# UART_to_USB-OTG_USB.net
KiCad netlist of a schematic drawn in Altium Designer
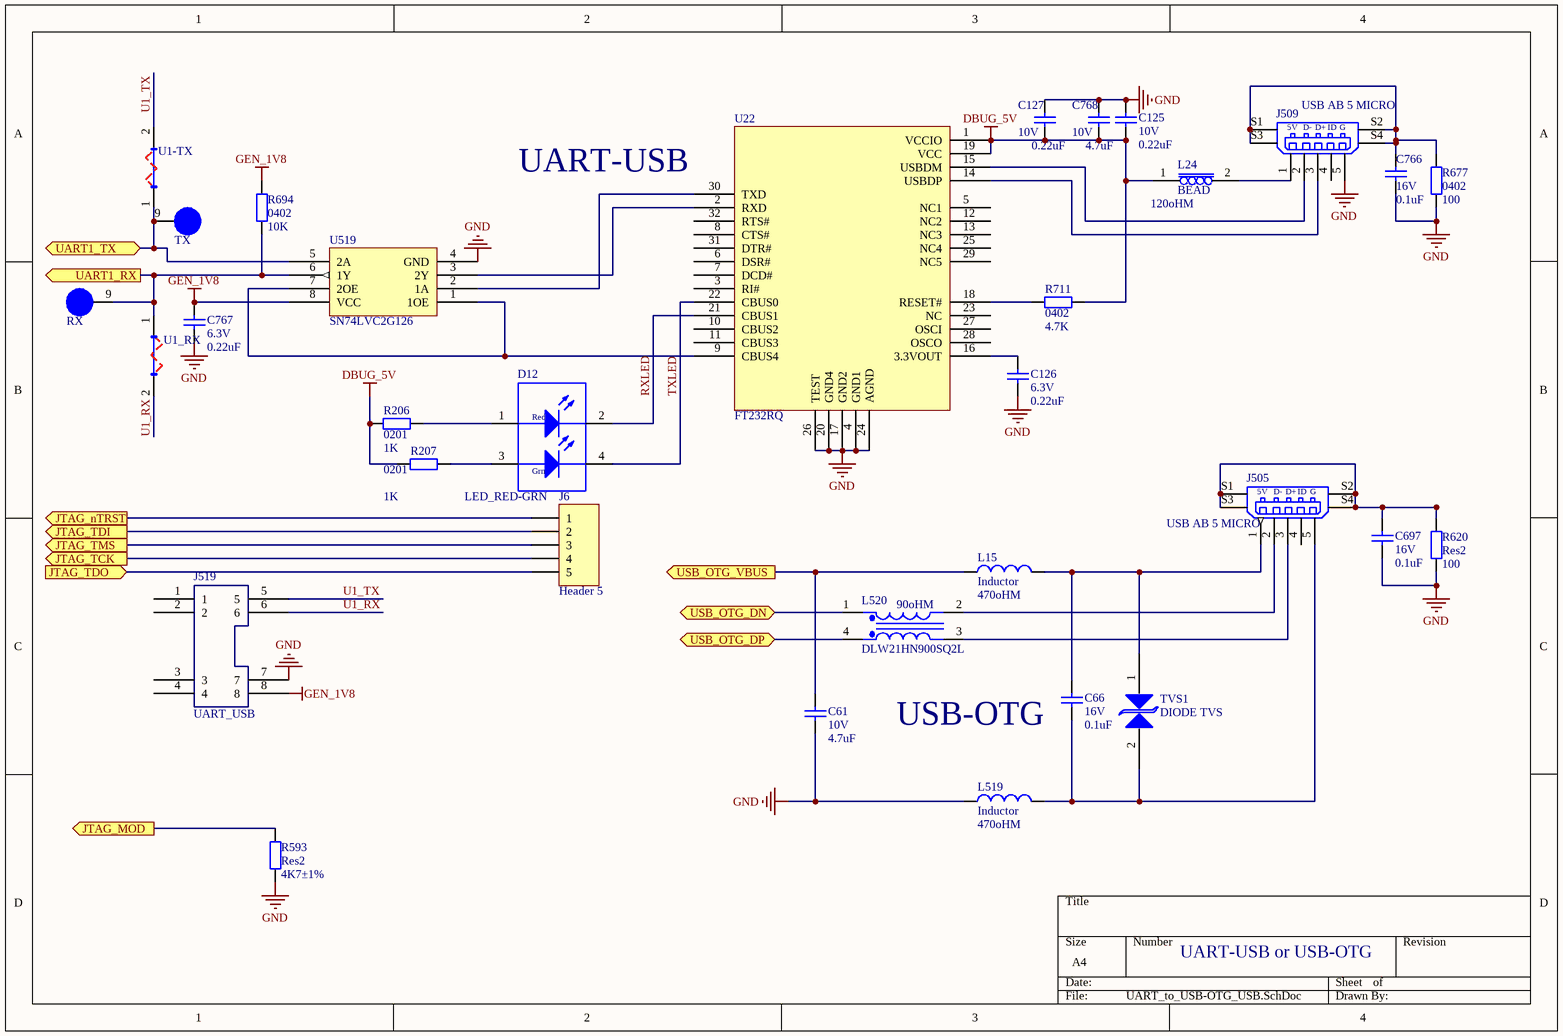
[diagram p0: UART_to_USB-OTG_USB.SchDoc]

(export (version "E")
  (design (tool "Eeschema 10.0.6"))
  (components
    (comp (ref "C61")
      (value "10V")
      (footprint "0603")
      (description "Capacitor")
      (fields (field (name "ALTIUM_VALUE") "4.7uF") (field (name "PUBLISHER") "Altium Limited"))
      (libsource (lib "Miscellaneous Devices") (part "Cap"))
    )
    (comp (ref "C66")
      (value "16V")
      (footprint "0402")
      (description "Capacitor")
      (fields (field (name "ALTIUM_VALUE") "0.1uF") (field (name "PUBLISHER") "Altium Limited"))
      (libsource (lib "Miscellaneous Devices") (part "Cap"))
    )
    (comp (ref "C125")
      (value "10V")
      (footprint "0201")
      (description "Capacitor")
      (fields (field (name "ALTIUM_VALUE") "0.22uF") (field (name "PUBLISHER") "Altium Limited"))
      (libsource (lib "Miscellaneous Devices") (part "Cap"))
    )
    (comp (ref "C126")
      (value "6.3V")
      (footprint "0201")
      (description "Capacitor")
      (fields (field (name "ALTIUM_VALUE") "0.22uF") (field (name "PUBLISHER") "Altium Limited"))
      (libsource (lib "Miscellaneous Devices") (part "Cap"))
    )
    (comp (ref "C127")
      (value "10V")
      (footprint "0201")
      (description "Capacitor")
      (fields (field (name "ALTIUM_VALUE") "0.22uF") (field (name "PUBLISHER") "Altium Limited"))
      (libsource (lib "Miscellaneous Devices") (part "Cap"))
    )
    (comp (ref "C697")
      (value "16V")
      (footprint "0402")
      (description "Capacitor")
      (fields (field (name "ALTIUM_VALUE") "0.1uF") (field (name "PUBLISHER") "Altium Limited"))
      (libsource (lib "Miscellaneous Devices") (part "Cap"))
    )
    (comp (ref "C766")
      (value "16V")
      (footprint "0402")
      (description "Capacitor")
      (fields (field (name "ALTIUM_VALUE") "0.1uF") (field (name "PUBLISHER") "Altium Limited"))
      (libsource (lib "Miscellaneous Devices") (part "Cap"))
    )
    (comp (ref "C767")
      (value "6.3V")
      (footprint "0201")
      (description "Capacitor")
      (fields (field (name "ALTIUM_VALUE") "0.22uF") (field (name "PUBLISHER") "Altium Limited"))
      (libsource (lib "Miscellaneous Devices") (part "Cap"))
    )
    (comp (ref "C768")
      (value "10V")
      (footprint "0603")
      (description "Capacitor")
      (fields (field (name "ALTIUM_VALUE") "4.7uF") (field (name "PUBLISHER") "Altium Limited"))
      (libsource (lib "Miscellaneous Devices") (part "Cap"))
    )
    (comp (ref "D12")
      (value "LED_RED-GRN")
      (footprint "APB3025ESGC-F01-SMT")
      (libsource (lib "IMX6DL") (part "APB3025ESGC-F01"))
    )
    (comp (ref "J6")
      (value "Header 5")
      (footprint "HDR1X5")
      (description "Header, 5-Pin")
      (fields (field (name "PUBLISHER") "Altium Limited"))
      (libsource (lib "Miscellaneous Connectors") (part "Header 5"))
    )
    (comp (ref "J505")
      (value "USB AB 5 MICRO")
      (footprint "micro-USB-port")
      (libsource (lib "IMX6DL") (part "USB AB 5 MICRO"))
    )
    (comp (ref "J509")
      (value "USB AB 5 MICRO")
      (footprint "micro-USB-port")
      (libsource (lib "IMX6DL") (part "USB AB 5 MICRO"))
    )
    (comp (ref "J519")
      (value "UART_USB")
      (footprint "DC3-8")
      (libsource (lib "IMX6DL") (part "JTAG_hornsocket8P"))
    )
    (comp (ref "L15")
      (value "Inductor")
      (footprint "0603")
      (fields (field (name "ALTIUM_VALUE") "470oHM") (field (name "PUBLISHER") "Altium Limited"))
      (libsource (lib "Miscellaneous Devices") (part "Inductor"))
    )
    (comp (ref "L24")
      (value "BEAD")
      (footprint "0603")
      (fields (field (name "ALTIUM_UNNAMED_1") "120oHM"))
      (libsource (lib "IMX6DL") (part "magnetic BEAD"))
    )
    (comp (ref "L519")
      (value "Inductor")
      (footprint "0603")
      (fields (field (name "ALTIUM_VALUE") "470oHM") (field (name "PUBLISHER") "Altium Limited"))
      (libsource (lib "Miscellaneous Devices") (part "Inductor"))
    )
    (comp (ref "L520")
      (value "DLW21HN900SQ2L")
      (footprint "DLW21HN900SQ2L-0805")
      (fields (field (name "ALTIUM_UNNAMED_1") "90oHM"))
      (libsource (lib "IMX6DL") (part "DLW21HN900SQ2L"))
    )
    (comp (ref "R206")
      (value "0201")
      (footprint "0201")
      (description "Resistor")
      (fields (field (name "ALTIUM_VALUE") "1K") (field (name "PUBLISHER") "Altium Limited"))
      (libsource (lib "Miscellaneous Devices") (part "Res2"))
    )
    (comp (ref "R207")
      (value "0201")
      (footprint "0201")
      (description "Resistor")
      (fields (field (name "ALTIUM_VALUE") "1K") (field (name "PUBLISHER") "Altium Limited"))
      (libsource (lib "Miscellaneous Devices") (part "Res2"))
    )
    (comp (ref "R593")
      (value "Res2")
      (footprint "0402")
      (description "Resistor")
      (fields (field (name "ALTIUM_VALUE") "4K7±1%") (field (name "PUBLISHER") "Altium Limited"))
      (libsource (lib "") (part "Res2_1"))
    )
    (comp (ref "R620")
      (value "Res2")
      (footprint "0402")
      (description "Resistor")
      (fields (field (name "ALTIUM_VALUE") "100") (field (name "PUBLISHER") "Altium Limited"))
      (libsource (lib "") (part "Res2_1"))
    )
    (comp (ref "R677")
      (value "0402")
      (footprint "0402")
      (description "Resistor")
      (fields (field (name "ALTIUM_VALUE") "100") (field (name "PUBLISHER") "Altium Limited"))
      (libsource (lib "") (part "Res2_1"))
    )
    (comp (ref "R694")
      (value "0402")
      (footprint "0402")
      (description "Resistor")
      (fields (field (name "ALTIUM_VALUE") "10K") (field (name "PUBLISHER") "Altium Limited"))
      (libsource (lib "") (part "Res2_1"))
    )
    (comp (ref "R711")
      (value "0402")
      (footprint "0402")
      (description "Resistor")
      (fields (field (name "ALTIUM_VALUE") "4.7K") (field (name "PUBLISHER") "Altium Limited"))
      (libsource (lib "Miscellaneous Devices") (part "Res2"))
    )
    (comp (ref "RX") (value "TP test") (footprint "TP") (libsource (lib "IMX6DL") (part "TP test")))
    (comp (ref "TVS1")
      (value "DIODE TVS")
      (footprint "ESD9B3.3ST5G-SOD923")
      (libsource (lib "IMX6DL") (part "DIODE TVS"))
    )
    (comp (ref "TX") (value "TP test") (footprint "TP") (libsource (lib "IMX6DL") (part "TP test")))
    (comp (ref "U1-TX")
      (value "SHORT")
      (footprint "SHORT_SH")
      (libsource (lib "IMX6DL") (part "SOLDER SHORT"))
    )
    (comp (ref "U1_RX")
      (value "SHORT")
      (footprint "SHORT_SH")
      (libsource (lib "IMX6DL") (part "SOLDER SHORT"))
    )
    (comp (ref "U22")
      (value "FT232RQ")
      (footprint "FT232RQ-QFN32")
      (libsource (lib "IMX6DL") (part "FT232RQ"))
    )
    (comp (ref "U519")
      (value "SN74LVC2G126")
      (footprint "SN74LVC2G126-SSOP8")
      (libsource (lib "IMX6DL") (part "SN74LVC2G126"))
    )
  )
  (nets
    (net (code "1") (name "/JTAG_MOD") (class "Default")
      (node (ref "R593") (pin "2") (pinfunction "2_2") (pintype "passive"))
    )
    (net (code "2") (name "/JTAG_TCK") (class "Default")
      (node (ref "J6") (pin "4") (pinfunction "4_4") (pintype "passive"))
    )
    (net (code "3") (name "/JTAG_TDI") (class "Default")
      (node (ref "J6") (pin "2") (pinfunction "2_2") (pintype "passive"))
    )
    (net (code "4") (name "/JTAG_TDO") (class "Default")
      (node (ref "J6") (pin "5") (pinfunction "5_5") (pintype "passive"))
    )
    (net (code "5") (name "/JTAG_TMS") (class "Default")
      (node (ref "J6") (pin "3") (pinfunction "3_3") (pintype "passive"))
    )
    (net (code "6") (name "/JTAG_nTRST") (class "Default")
      (node (ref "J6") (pin "1") (pinfunction "1_1") (pintype "passive"))
    )
    (net (code "7") (name "/RXLED") (class "Default")
      (node (ref "D12") (pin "2") (pinfunction "GND_2") (pintype "passive"))
      (node (ref "U22") (pin "21") (pinfunction "CBUS1_21") (pintype "passive"))
    )
    (net (code "8") (name "/TXLED") (class "Default")
      (node (ref "D12") (pin "4") (pinfunction "GND_4") (pintype "passive"))
      (node (ref "U22") (pin "22") (pinfunction "CBUS0_22") (pintype "passive"))
    )
    (net (code "9") (name "/U1_RX") (class "Default")
      (node (ref "J519") (pin "6") (pinfunction "6_6") (pintype "passive"))
      (node (ref "U1_RX") (pin "2") (pinfunction "VCCIO_2") (pintype "passive"))
    )
    (net (code "10") (name "/U1_TX") (class "Default")
      (node (ref "J519") (pin "5") (pinfunction "5_5") (pintype "passive"))
      (node (ref "U1-TX") (pin "2") (pinfunction "VCCIO_2") (pintype "passive"))
    )
    (net (code "11") (name "/UART1_RX") (class "Default")
      (node (ref "R694") (pin "1") (pinfunction "1_1") (pintype "passive"))
      (node (ref "RX") (pin "9") (pinfunction "S_9") (pintype "passive"))
      (node (ref "U1_RX") (pin "1") (pinfunction "VCCIO_1") (pintype "passive"))
      (node (ref "U519") (pin "6") (pinfunction "1Y_6") (pintype "output"))
    )
    (net (code "12") (name "/UART1_TX") (class "Default")
      (node (ref "TX") (pin "9") (pinfunction "S_9") (pintype "passive"))
      (node (ref "U1-TX") (pin "1") (pinfunction "VCCIO_1") (pintype "passive"))
      (node (ref "U519") (pin "5") (pinfunction "2A_5") (pintype "passive"))
    )
    (net (code "13") (name "/USB_OTG_DN") (class "Default")
      (node (ref "L520") (pin "1") (pinfunction "VSS11_1") (pintype "passive"))
    )
    (net (code "14") (name "/USB_OTG_DP") (class "Default")
      (node (ref "L520") (pin "4") (pinfunction "VSS14_4") (pintype "passive"))
    )
    (net (code "15") (name "/USB_OTG_VBUS") (class "Default")
      (node (ref "C61") (pin "2") (pinfunction "2_2") (pintype "passive"))
      (node (ref "L15") (pin "1") (pinfunction "1_1") (pintype "passive"))
    )
    (net (code "16") (name "DBUG_5V") (class "Default")
      (node (ref "C125") (pin "2") (pinfunction "2_2") (pintype "passive"))
      (node (ref "C127") (pin "2") (pinfunction "2_2") (pintype "passive"))
      (node (ref "C768") (pin "1") (pinfunction "1_1") (pintype "passive"))
      (node (ref "L24") (pin "1") (pinfunction "VSS3_1") (pintype "passive"))
      (node (ref "R206") (pin "1") (pinfunction "1_1") (pintype "passive"))
      (node (ref "R207") (pin "1") (pinfunction "1_1") (pintype "passive"))
      (node (ref "R711") (pin "2") (pinfunction "2_2") (pintype "passive"))
      (node (ref "U22") (pin "1") (pinfunction "VCCIO_1") (pintype "passive"))
      (node (ref "U22") (pin "19") (pinfunction "VCC_19") (pintype "passive"))
    )
    (net (code "17") (name "GEN_1V8") (class "Default")
      (node (ref "C767") (pin "1") (pinfunction "1_1") (pintype "passive"))
      (node (ref "J519") (pin "8") (pinfunction "8_8") (pintype "passive"))
      (node (ref "R694") (pin "2") (pinfunction "2_2") (pintype "passive"))
      (node (ref "U519") (pin "8") (pinfunction "VCC_8") (pintype "passive"))
    )
    (net (code "18") (name "GND") (class "Default")
      (node (ref "C125") (pin "1") (pinfunction "1_1") (pintype "passive"))
      (node (ref "C126") (pin "2") (pinfunction "2_2") (pintype "passive"))
      (node (ref "C127") (pin "1") (pinfunction "1_1") (pintype "passive"))
      (node (ref "C61") (pin "1") (pinfunction "1_1") (pintype "passive"))
      (node (ref "C697") (pin "1") (pinfunction "1_1") (pintype "passive"))
      (node (ref "C766") (pin "1") (pinfunction "1_1") (pintype "passive"))
      (node (ref "C767") (pin "2") (pinfunction "2_2") (pintype "passive"))
      (node (ref "C768") (pin "2") (pinfunction "2_2") (pintype "passive"))
      (node (ref "J509") (pin "5") (pinfunction "GND_5") (pintype "passive"))
      (node (ref "J519") (pin "7") (pinfunction "7_7") (pintype "passive"))
      (node (ref "L519") (pin "1") (pinfunction "1_1") (pintype "passive"))
      (node (ref "R593") (pin "1") (pinfunction "1_1") (pintype "passive"))
      (node (ref "R620") (pin "1") (pinfunction "1_1") (pintype "passive"))
      (node (ref "R677") (pin "1") (pinfunction "1_1") (pintype "passive"))
      (node (ref "U22") (pin "17") (pinfunction "GND2_17") (pintype "passive"))
      (node (ref "U22") (pin "20") (pinfunction "GND4_20") (pintype "passive"))
      (node (ref "U22") (pin "24") (pinfunction "AGND_24") (pintype "passive"))
      (node (ref "U22") (pin "26") (pinfunction "TEST_26") (pintype "passive"))
      (node (ref "U22") (pin "4") (pinfunction "GND1_4") (pintype "passive"))
      (node (ref "U519") (pin "4") (pinfunction "GND_4") (pintype "passive"))
    )
    (net (code "19") (name "Net-(D12-GND-Pad1)") (class "Default")
      (node (ref "D12") (pin "1") (pinfunction "GND_1") (pintype "passive"))
      (node (ref "R206") (pin "2") (pinfunction "2_2") (pintype "passive"))
    )
    (net (code "20") (name "Net-(D12-GND-Pad3)") (class "Default")
      (node (ref "D12") (pin "3") (pinfunction "GND_3") (pintype "passive"))
      (node (ref "R207") (pin "2") (pinfunction "2_2") (pintype "passive"))
    )
    (net (code "21") (name "Net-(J505-6)") (class "Default")
      (node (ref "C697") (pin "2") (pinfunction "2_2") (pintype "passive"))
      (node (ref "J505") (pin "S1") (pinfunction "6_S1") (pintype "passive"))
      (node (ref "J505") (pin "S2") (pinfunction "7_S2") (pintype "passive"))
      (node (ref "J505") (pin "S3") (pinfunction "8_S3") (pintype "passive"))
      (node (ref "J505") (pin "S4") (pinfunction "9_S4") (pintype "passive"))
      (node (ref "R620") (pin "2") (pinfunction "2_2") (pintype "passive"))
    )
    (net (code "22") (name "Net-(J509-6)") (class "Default")
      (node (ref "C766") (pin "2") (pinfunction "2_2") (pintype "passive"))
      (node (ref "J509") (pin "S1") (pinfunction "6_S1") (pintype "passive"))
      (node (ref "J509") (pin "S2") (pinfunction "7_S2") (pintype "passive"))
      (node (ref "J509") (pin "S3") (pinfunction "8_S3") (pintype "passive"))
      (node (ref "J509") (pin "S4") (pinfunction "9_S4") (pintype "passive"))
      (node (ref "R677") (pin "2") (pinfunction "2_2") (pintype "passive"))
    )
    (net (code "23") (name "Net-(L24-VSS4)") (class "Default")
      (node (ref "J509") (pin "1") (pinfunction "GND_1") (pintype "passive"))
      (node (ref "L24") (pin "2") (pinfunction "VSS4_2") (pintype "passive"))
    )
    (net (code "24") (name "Net-(L520-VSS12)") (class "Default")
      (node (ref "J505") (pin "2") (pinfunction "GND_2") (pintype "passive"))
      (node (ref "L520") (pin "2") (pinfunction "VSS12_2") (pintype "passive"))
    )
    (net (code "25") (name "Net-(L520-VSS13)") (class "Default")
      (node (ref "J505") (pin "3") (pinfunction "GND_3") (pintype "passive"))
      (node (ref "L520") (pin "3") (pinfunction "VSS13_3") (pintype "passive"))
    )
    (net (code "26") (name "Net-(TVS1-VSS5)") (class "Default")
      (node (ref "C66") (pin "1") (pinfunction "1_1") (pintype "passive"))
      (node (ref "J505") (pin "5") (pinfunction "GND_5") (pintype "passive"))
      (node (ref "L519") (pin "2") (pinfunction "2_2") (pintype "passive"))
      (node (ref "TVS1") (pin "2") (pinfunction "VSS5_2") (pintype "passive"))
    )
    (net (code "27") (name "Net-(TVS1-VSS6)") (class "Default")
      (node (ref "C66") (pin "2") (pinfunction "2_2") (pintype "passive"))
      (node (ref "J505") (pin "1") (pinfunction "GND_1") (pintype "passive"))
      (node (ref "L15") (pin "2") (pinfunction "2_2") (pintype "passive"))
      (node (ref "TVS1") (pin "1") (pinfunction "VSS6_1") (pintype "passive"))
    )
    (net (code "28") (name "Net-(U22-3.3VOUT)") (class "Default")
      (node (ref "C126") (pin "1") (pinfunction "1_1") (pintype "passive"))
      (node (ref "U22") (pin "16") (pinfunction "3.3VOUT_16") (pintype "passive"))
    )
    (net (code "29") (name "Net-(U22-CBUS4)") (class "Default")
      (node (ref "U22") (pin "9") (pinfunction "CBUS4_9") (pintype "passive"))
      (node (ref "U519") (pin "1") (pinfunction "1OE_1") (pintype "passive"))
      (node (ref "U519") (pin "7") (pinfunction "2OE_7") (pintype "passive"))
    )
    (net (code "30") (name "Net-(U22-RESET#)") (class "Default")
      (node (ref "R711") (pin "1") (pinfunction "1_1") (pintype "passive"))
      (node (ref "U22") (pin "18") (pinfunction "RESET#_18") (pintype "passive"))
    )
    (net (code "31") (name "Net-(U22-RXD)") (class "Default")
      (node (ref "U22") (pin "2") (pinfunction "RXD_2") (pintype "passive"))
      (node (ref "U519") (pin "3") (pinfunction "2Y_3") (pintype "passive"))
    )
    (net (code "32") (name "Net-(U22-TXD)") (class "Default")
      (node (ref "U22") (pin "30") (pinfunction "TXD_30") (pintype "passive"))
      (node (ref "U519") (pin "2") (pinfunction "1A_2") (pintype "passive"))
    )
    (net (code "33") (name "Net-(U22-USBDM)") (class "Default")
      (node (ref "J509") (pin "2") (pinfunction "GND_2") (pintype "passive"))
      (node (ref "U22") (pin "15") (pinfunction "USBDM_15") (pintype "passive"))
    )
    (net (code "34") (name "Net-(U22-USBDP)") (class "Default")
      (node (ref "J509") (pin "3") (pinfunction "GND_3") (pintype "passive"))
      (node (ref "U22") (pin "14") (pinfunction "USBDP_14") (pintype "passive"))
    )
    (net (code "35") (name "unconnected-(J505-GND-Pad4)") (class "Default")
      (node (ref "J505") (pin "4") (pinfunction "GND_4") (pintype "passive"))
    )
    (net (code "36") (name "unconnected-(J509-GND-Pad4)") (class "Default")
      (node (ref "J509") (pin "4") (pinfunction "GND_4") (pintype "passive"))
    )
    (net (code "37") (name "unconnected-(J519-Pad1)") (class "Default")
      (node (ref "J519") (pin "1") (pinfunction "1_1") (pintype "passive"))
    )
    (net (code "38") (name "unconnected-(J519-Pad2)") (class "Default")
      (node (ref "J519") (pin "2") (pinfunction "2_2") (pintype "passive"))
    )
    (net (code "39") (name "unconnected-(J519-Pad3)") (class "Default")
      (node (ref "J519") (pin "3") (pinfunction "3_3") (pintype "passive"))
    )
    (net (code "40") (name "unconnected-(J519-Pad4)") (class "Default")
      (node (ref "J519") (pin "4") (pinfunction "4_4") (pintype "passive"))
    )
    (net (code "41") (name "unconnected-(U22-CBUS2-Pad10)") (class "Default")
      (node (ref "U22") (pin "10") (pinfunction "CBUS2_10") (pintype "passive"))
    )
    (net (code "42") (name "unconnected-(U22-CBUS3-Pad11)") (class "Default")
      (node (ref "U22") (pin "11") (pinfunction "CBUS3_11") (pintype "passive"))
    )
    (net (code "43") (name "unconnected-(U22-CTS#-Pad8)") (class "Default")
      (node (ref "U22") (pin "8") (pinfunction "CTS#_8") (pintype "passive"))
    )
    (net (code "44") (name "unconnected-(U22-DCD#-Pad7)") (class "Default")
      (node (ref "U22") (pin "7") (pinfunction "DCD#_7") (pintype "passive"))
    )
    (net (code "45") (name "unconnected-(U22-DSR#-Pad6)") (class "Default")
      (node (ref "U22") (pin "6") (pinfunction "DSR#_6") (pintype "passive"))
    )
    (net (code "46") (name "unconnected-(U22-DTR#-Pad31)") (class "Default")
      (node (ref "U22") (pin "31") (pinfunction "DTR#_31") (pintype "passive"))
    )
    (net (code "47") (name "unconnected-(U22-NC-Pad23)") (class "Default")
      (node (ref "U22") (pin "23") (pinfunction "NC_23") (pintype "passive"))
    )
    (net (code "48") (name "unconnected-(U22-NC1-Pad5)") (class "Default")
      (node (ref "U22") (pin "5") (pinfunction "NC1_5") (pintype "passive"))
    )
    (net (code "49") (name "unconnected-(U22-NC2-Pad12)") (class "Default")
      (node (ref "U22") (pin "12") (pinfunction "NC2_12") (pintype "passive"))
    )
    (net (code "50") (name "unconnected-(U22-NC3-Pad13)") (class "Default")
      (node (ref "U22") (pin "13") (pinfunction "NC3_13") (pintype "passive"))
    )
    (net (code "51") (name "unconnected-(U22-NC4-Pad25)") (class "Default")
      (node (ref "U22") (pin "25") (pinfunction "NC4_25") (pintype "passive"))
    )
    (net (code "52") (name "unconnected-(U22-NC5-Pad29)") (class "Default")
      (node (ref "U22") (pin "29") (pinfunction "NC5_29") (pintype "passive"))
    )
    (net (code "53") (name "unconnected-(U22-OSCI-Pad27)") (class "Default")
      (node (ref "U22") (pin "27") (pinfunction "OSCI_27") (pintype "passive"))
    )
    (net (code "54") (name "unconnected-(U22-OSCO-Pad28)") (class "Default")
      (node (ref "U22") (pin "28") (pinfunction "OSCO_28") (pintype "passive"))
    )
    (net (code "55") (name "unconnected-(U22-RI#-Pad3)") (class "Default")
      (node (ref "U22") (pin "3") (pinfunction "RI#_3") (pintype "passive"))
    )
    (net (code "56") (name "unconnected-(U22-RTS#-Pad32)") (class "Default")
      (node (ref "U22") (pin "32") (pinfunction "RTS#_32") (pintype "passive"))
    )
  )
)
